# CPU.net
KiCad netlist of a schematic drawn in Altium Designer
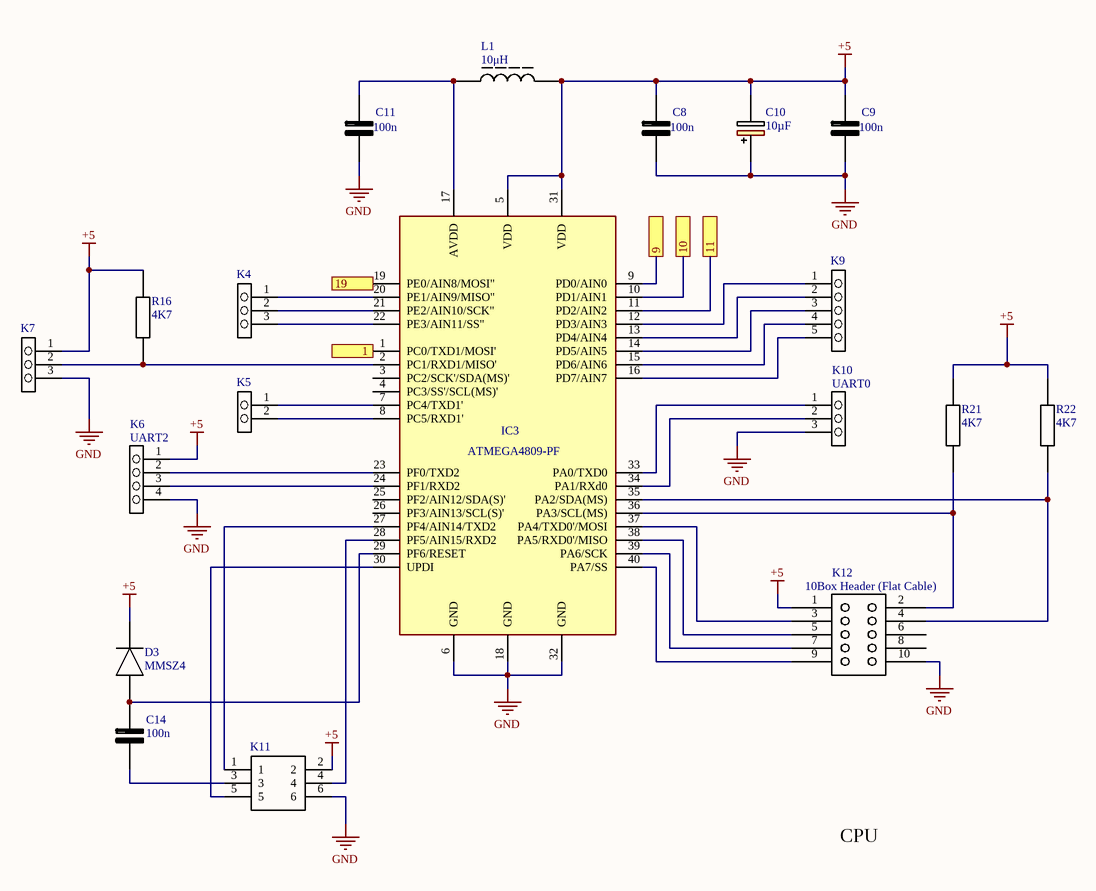
[diagram p0: CPU.SchDoc]

(export (version "E")
  (design (tool "Eeschema 10.0.6"))
  (components
    (comp (ref "C8")
      (value "100n")
      (footprint "SamacSys:C0805")
      (description "Capacitor")
      (fields (field (name "MANUFACTURER_PART_NUMBER") "C0805C391G3GACTU"))
      (libsource (lib "SamacSys") (part "0805_1"))
    )
    (comp (ref "C9")
      (value "100n")
      (footprint "SamacSys:C0805")
      (description "Capacitor")
      (fields (field (name "MANUFACTURER_PART_NUMBER") "C0805C391G3GACTU"))
      (libsource (lib "SamacSys") (part "0805_1"))
    )
    (comp (ref "C10")
      (value "10µF")
      (footprint "SamacSys:CAPPRD200W52D500H1250")
      (description "Capacitor Polarised")
      (fields
        (field (name "MOUSER2 PART NUMBER") "710-860020672010")
        (field (name "MANUFACTURER_PART_NUMBER") "860020672010")
      )
      (libsource (lib "SamacSys") (part "860020672010"))
    )
    (comp (ref "C11")
      (value "100n")
      (footprint "SamacSys:C0805")
      (description "Capacitor")
      (fields (field (name "MANUFACTURER_PART_NUMBER") "C0805C391G3GACTU"))
      (libsource (lib "SamacSys") (part "0805_1"))
    )
    (comp (ref "C14")
      (value "100n")
      (footprint "SamacSys:C0805")
      (description "Capacitor")
      (fields (field (name "MANUFACTURER_PART_NUMBER") "C0805C391G3GACTU"))
      (libsource (lib "SamacSys") (part "0805_1"))
    )
    (comp (ref "D3")
      (value "MMSZ4")
      (footprint "SamacSys:SOD2512X110N")
      (description "Diode")
      (fields
        (field (name "MOUSER2 PART NUMBER") "863-SMMDL914T1G")
        (field (name "MANUFACTURER_PART_NUMBER") "SMMDL914T1G")
      )
      (libsource (lib "SamacSys") (part "SMMDL914T1G"))
    )
    (comp (ref "IC3")
      (value "ATMEGA4809-PF")
      (footprint "SamacSys:DIP1543W58P254L5175H635Q40N")
      (description "Integrated Circuit")
      (fields (field (name "MOUSER2 PART NUMBER") "556-ATMEGA4809-PF"))
      (libsource (lib "SamacSys") (part "ATMEGA4809-PF"))
    )
    (comp (ref "K4")
      (value "M20-9990345")
      (footprint "SamacSys:HDRV3W64P0X254_1X3_762X254X864P")
      (description "Connector 3-PIN")
      (fields (field (name "MOUSER2 PART NUMBER") "855-M20-9990345"))
      (libsource (lib "SamacSys") (part "M20-9990345"))
    )
    (comp (ref "K5")
      (value "M20-9990246")
      (footprint "SamacSys:HDRV2W66P0X254_1X2_508X254X874P")
      (description "Connector 2-PIN")
      (fields (field (name "MOUSER2 PART NUMBER") "855-M20-9990246"))
      (libsource (lib "SamacSys") (part "M20-9990246"))
    )
    (comp (ref "K6")
      (value "UART2")
      (footprint "SamacSys:HDRV4W64P0X254_1X4_1016X254X834P")
      (description "Connector 4-PIN")
      (fields
        (field (name "MOUSER2 PART NUMBER") "855-M20-9770446")
        (field (name "MANUFACTURER_PART_NUMBER") "M20-9770446")
      )
      (libsource (lib "SamacSys") (part "M20-9770446"))
    )
    (comp (ref "K7")
      (value "M20-9990345")
      (footprint "SamacSys:HDRV3W64P0X254_1X3_762X254X864P")
      (description "Connector 3-PIN")
      (fields (field (name "MOUSER2 PART NUMBER") "855-M20-9990345"))
      (libsource (lib "SamacSys") (part "M20-9990345"))
    )
    (comp (ref "K9")
      (value "M20-9990545")
      (footprint "SamacSys:HDRV5W64P0X254_1X5_1270X254X864P")
      (description "Connector 5-PIN")
      (fields (field (name "MOUSER2 PART NUMBER") "855-M20-9990545"))
      (libsource (lib "SamacSys") (part "M20-9990545"))
    )
    (comp (ref "K10")
      (value "UART0")
      (footprint "SamacSys:HDRV3W64P0X254_1X3_762X254X864P")
      (description "Connector 3-PIN")
      (fields
        (field (name "MOUSER2 PART NUMBER") "855-M20-9990345")
        (field (name "MANUFACTURER_PART_NUMBER") "M20-9990345")
      )
      (libsource (lib "") (part "M20-9990345_1"))
    )
    (comp (ref "K11")
      (value "M20-9760342")
      (footprint "SamacSys:HDRV6W66P254_2X3_762X508X830P")
      (description "Connector 6-PIN")
      (libsource (lib "SamacSys") (part "M20-9760342"))
    )
    (comp (ref "K12")
      (value "10Box Header (Flat Cable)")
      (footprint "SamacSys:10BoxHeader")
      (libsource (lib "SamacSys") (part "10Box Header (Flat Cable)"))
    )
    (comp (ref "L1")
      (value "10μH")
      (footprint "SamacSys:VLS56045")
      (description "Inductor")
      (fields
        (field (name "MOUSER2 PART NUMBER") "810-VLS6045EX-100M-H")
        (field (name "MANUFACTURER_PART_NUMBER") "VLS6045EX-100M-H")
      )
      (libsource (lib "SamacSys") (part "VLS6045EX-100M-H"))
    )
    (comp (ref "R16")
      (value "4K7")
      (footprint "SamacSys:C0805")
      (description "Resistor")
      (fields (field (name "MANUFACTURER_PART_NUMBER") "C0805C391G3GACTU"))
      (libsource (lib "SamacSys") (part "0805"))
    )
    (comp (ref "R21")
      (value "4K7")
      (footprint "SamacSys:C0805")
      (description "Resistor")
      (fields (field (name "MANUFACTURER_PART_NUMBER") "C0805C391G3GACTU"))
      (libsource (lib "SamacSys") (part "0805"))
    )
    (comp (ref "R22")
      (value "4K7")
      (footprint "SamacSys:C0805")
      (description "Resistor")
      (fields (field (name "MANUFACTURER_PART_NUMBER") "C0805C391G3GACTU"))
      (libsource (lib "SamacSys") (part "0805"))
    )
  )
  (nets
    (net (code "1") (name "+5") (class "Default")
      (node (ref "C10") (pin "2") (pinfunction "-_2") (pintype "passive"))
      (node (ref "C8") (pin "2") (pinfunction "-_2") (pintype "passive"))
      (node (ref "C9") (pin "2") (pinfunction "-_2") (pintype "passive"))
      (node (ref "D3") (pin "1") (pinfunction "K_1") (pintype "passive"))
      (node (ref "IC3") (pin "31") (pinfunction "VDD_31") (pintype "passive"))
      (node (ref "IC3") (pin "5") (pinfunction "VDD_5") (pintype "passive"))
      (node (ref "K11") (pin "2") (pinfunction "2_2") (pintype "passive"))
      (node (ref "K12") (pin "1") (pinfunction "1_1") (pintype "passive"))
      (node (ref "K6") (pin "1") (pinfunction "1_1") (pintype "passive"))
      (node (ref "K7") (pin "1") (pinfunction "1_1") (pintype "passive"))
      (node (ref "L1") (pin "2") (pinfunction "2_2") (pintype "passive"))
      (node (ref "R16") (pin "2") (pinfunction "2_2") (pintype "passive"))
      (node (ref "R21") (pin "2") (pinfunction "2_2") (pintype "passive"))
      (node (ref "R22") (pin "2") (pinfunction "2_2") (pintype "passive"))
    )
    (net (code "2") (name "/1") (class "Default")
      (node (ref "IC3") (pin "1") (pinfunction "PC0/TXD1/MOSI'_1") (pintype "passive"))
    )
    (net (code "3") (name "/9") (class "Default")
      (node (ref "IC3") (pin "9") (pinfunction "PD0/AIN0_9") (pintype "passive"))
    )
    (net (code "4") (name "/10") (class "Default")
      (node (ref "IC3") (pin "10") (pinfunction "PD1/AIN1_10") (pintype "passive"))
    )
    (net (code "5") (name "/11") (class "Default")
      (node (ref "IC3") (pin "11") (pinfunction "PD2/AIN2_11") (pintype "passive"))
    )
    (net (code "6") (name "/19") (class "Default")
      (node (ref "IC3") (pin "19") (pinfunction "PE0/AIN8/MOSI\"_19") (pintype "passive"))
    )
    (net (code "7") (name "GND") (class "Default")
      (node (ref "C10") (pin "1") (pinfunction "+_1") (pintype "passive"))
      (node (ref "C11") (pin "1") (pinfunction "+_1") (pintype "passive"))
      (node (ref "C8") (pin "1") (pinfunction "+_1") (pintype "passive"))
      (node (ref "C9") (pin "1") (pinfunction "+_1") (pintype "passive"))
      (node (ref "IC3") (pin "18") (pinfunction "GND_18") (pintype "passive"))
      (node (ref "IC3") (pin "32") (pinfunction "GND_32") (pintype "passive"))
      (node (ref "IC3") (pin "6") (pinfunction "GND_6") (pintype "passive"))
      (node (ref "K10") (pin "3") (pinfunction "3_3") (pintype "passive"))
      (node (ref "K11") (pin "6") (pinfunction "6_6") (pintype "passive"))
      (node (ref "K12") (pin "10") (pinfunction "10_10") (pintype "passive"))
      (node (ref "K6") (pin "4") (pinfunction "4_4") (pintype "passive"))
      (node (ref "K7") (pin "3") (pinfunction "3_3") (pintype "passive"))
    )
    (net (code "8") (name "Net-(C11--)") (class "Default")
      (node (ref "C11") (pin "2") (pinfunction "-_2") (pintype "passive"))
      (node (ref "IC3") (pin "17") (pinfunction "AVDD_17") (pintype "passive"))
      (node (ref "L1") (pin "1") (pinfunction "1_1") (pintype "passive"))
    )
    (net (code "9") (name "Net-(C14-+)") (class "Default")
      (node (ref "C14") (pin "1") (pinfunction "+_1") (pintype "passive"))
      (node (ref "K11") (pin "3") (pinfunction "3_3") (pintype "passive"))
    )
    (net (code "10") (name "Net-(C14--)") (class "Default")
      (node (ref "C14") (pin "2") (pinfunction "-_2") (pintype "passive"))
      (node (ref "D3") (pin "2") (pinfunction "A_2") (pintype "passive"))
      (node (ref "IC3") (pin "29") (pinfunction "PF6/RESET_29") (pintype "passive"))
    )
    (net (code "11") (name "Net-(IC3-PA0{slash}TXD0)") (class "Default")
      (node (ref "IC3") (pin "33") (pinfunction "PA0/TXD0_33") (pintype "passive"))
      (node (ref "K10") (pin "1") (pinfunction "1_1") (pintype "passive"))
    )
    (net (code "12") (name "Net-(IC3-PA1{slash}RXd0)") (class "Default")
      (node (ref "IC3") (pin "34") (pinfunction "PA1/RXd0_34") (pintype "passive"))
      (node (ref "K10") (pin "2") (pinfunction "2_2") (pintype "passive"))
    )
    (net (code "13") (name "Net-(IC3-PA2{slash}SDA(MS))") (class "Default")
      (node (ref "IC3") (pin "35") (pinfunction "PA2/SDA(MS)_35") (pintype "passive"))
      (node (ref "K12") (pin "4") (pinfunction "4_4") (pintype "passive"))
      (node (ref "R22") (pin "1") (pinfunction "1_1") (pintype "passive"))
    )
    (net (code "14") (name "Net-(IC3-PA3{slash}SCL(MS))") (class "Default")
      (node (ref "IC3") (pin "36") (pinfunction "PA3/SCL(MS)_36") (pintype "passive"))
      (node (ref "K12") (pin "2") (pinfunction "2_2") (pintype "passive"))
      (node (ref "R21") (pin "1") (pinfunction "1_1") (pintype "passive"))
    )
    (net (code "15") (name "Net-(IC3-PA4{slash}TXD0'{slash}MOSI)") (class "Default")
      (node (ref "IC3") (pin "37") (pinfunction "PA4/TXD0'/MOSI_37") (pintype "passive"))
      (node (ref "K12") (pin "3") (pinfunction "3_3") (pintype "passive"))
    )
    (net (code "16") (name "Net-(IC3-PA5{slash}RXD0'{slash}MISO)") (class "Default")
      (node (ref "IC3") (pin "38") (pinfunction "PA5/RXD0'/MISO_38") (pintype "passive"))
      (node (ref "K12") (pin "5") (pinfunction "5_5") (pintype "passive"))
    )
    (net (code "17") (name "Net-(IC3-PA6{slash}SCK)") (class "Default")
      (node (ref "IC3") (pin "39") (pinfunction "PA6/SCK_39") (pintype "passive"))
      (node (ref "K12") (pin "7") (pinfunction "7_7") (pintype "passive"))
    )
    (net (code "18") (name "Net-(IC3-PA7{slash}SS)") (class "Default")
      (node (ref "IC3") (pin "40") (pinfunction "PA7/SS_40") (pintype "passive"))
      (node (ref "K12") (pin "9") (pinfunction "9_9") (pintype "passive"))
    )
    (net (code "19") (name "Net-(IC3-PC1{slash}RXD1{slash}MISO')") (class "Default")
      (node (ref "IC3") (pin "2") (pinfunction "PC1/RXD1/MISO'_2") (pintype "passive"))
      (node (ref "K7") (pin "2") (pinfunction "2_2") (pintype "passive"))
      (node (ref "R16") (pin "1") (pinfunction "1_1") (pintype "passive"))
    )
    (net (code "20") (name "Net-(IC3-PC4{slash}TXD1')") (class "Default")
      (node (ref "IC3") (pin "7") (pinfunction "PC4/TXD1'_7") (pintype "passive"))
      (node (ref "K5") (pin "1") (pinfunction "1_1") (pintype "passive"))
    )
    (net (code "21") (name "Net-(IC3-PC5{slash}RXD1')") (class "Default")
      (node (ref "IC3") (pin "8") (pinfunction "PC5/RXD1'_8") (pintype "passive"))
      (node (ref "K5") (pin "2") (pinfunction "2_2") (pintype "passive"))
    )
    (net (code "22") (name "Net-(IC3-PD3{slash}AIN3)") (class "Default")
      (node (ref "IC3") (pin "12") (pinfunction "PD3/AIN3_12") (pintype "passive"))
      (node (ref "K9") (pin "1") (pinfunction "1_1") (pintype "passive"))
    )
    (net (code "23") (name "Net-(IC3-PD4{slash}AIN4)") (class "Default")
      (node (ref "IC3") (pin "13") (pinfunction "PD4/AIN4_13") (pintype "passive"))
      (node (ref "K9") (pin "2") (pinfunction "2_2") (pintype "passive"))
    )
    (net (code "24") (name "Net-(IC3-PD5{slash}AIN5)") (class "Default")
      (node (ref "IC3") (pin "14") (pinfunction "PD5/AIN5_14") (pintype "passive"))
      (node (ref "K9") (pin "3") (pinfunction "3_3") (pintype "passive"))
    )
    (net (code "25") (name "Net-(IC3-PD6{slash}AIN6)") (class "Default")
      (node (ref "IC3") (pin "15") (pinfunction "PD6/AIN6_15") (pintype "passive"))
      (node (ref "K9") (pin "4") (pinfunction "4_4") (pintype "passive"))
    )
    (net (code "26") (name "Net-(IC3-PD7{slash}AIN7)") (class "Default")
      (node (ref "IC3") (pin "16") (pinfunction "PD7/AIN7_16") (pintype "passive"))
      (node (ref "K9") (pin "5") (pinfunction "5_5") (pintype "passive"))
    )
    (net (code "27") (name "Net-(IC3-PE1{slash}AIN9{slash}MISO\")") (class "Default")
      (node (ref "IC3") (pin "20") (pinfunction "PE1/AIN9/MISO\"_20") (pintype "passive"))
      (node (ref "K4") (pin "1") (pinfunction "1_1") (pintype "passive"))
    )
    (net (code "28") (name "Net-(IC3-PE2{slash}AIN10{slash}SCK\")") (class "Default")
      (node (ref "IC3") (pin "21") (pinfunction "PE2/AIN10/SCK\"_21") (pintype "passive"))
      (node (ref "K4") (pin "2") (pinfunction "2_2") (pintype "passive"))
    )
    (net (code "29") (name "Net-(IC3-PE3{slash}AIN11{slash}SS\")") (class "Default")
      (node (ref "IC3") (pin "22") (pinfunction "PE3/AIN11/SS\"_22") (pintype "passive"))
      (node (ref "K4") (pin "3") (pinfunction "3_3") (pintype "passive"))
    )
    (net (code "30") (name "Net-(IC3-PF0{slash}TXD2)") (class "Default")
      (node (ref "IC3") (pin "23") (pinfunction "PF0/TXD2_23") (pintype "passive"))
      (node (ref "K6") (pin "2") (pinfunction "2_2") (pintype "passive"))
    )
    (net (code "31") (name "Net-(IC3-PF1{slash}RXD2)") (class "Default")
      (node (ref "IC3") (pin "24") (pinfunction "PF1/RXD2_24") (pintype "passive"))
      (node (ref "K6") (pin "3") (pinfunction "3_3") (pintype "passive"))
    )
    (net (code "32") (name "Net-(IC3-PF4{slash}AIN14{slash}TXD2)") (class "Default")
      (node (ref "IC3") (pin "27") (pinfunction "PF4/AIN14/TXD2_27") (pintype "passive"))
      (node (ref "K11") (pin "1") (pinfunction "1_1") (pintype "passive"))
    )
    (net (code "33") (name "Net-(IC3-PF5{slash}AIN15{slash}RXD2)") (class "Default")
      (node (ref "IC3") (pin "28") (pinfunction "PF5/AIN15/RXD2_28") (pintype "passive"))
      (node (ref "K11") (pin "4") (pinfunction "4_4") (pintype "passive"))
    )
    (net (code "34") (name "Net-(IC3-UPDI)") (class "Default")
      (node (ref "IC3") (pin "30") (pinfunction "UPDI_30") (pintype "passive"))
      (node (ref "K11") (pin "5") (pinfunction "5_5") (pintype "passive"))
    )
    (net (code "35") (name "unconnected-(IC3-PC2{slash}SCK'{slash}SDA(MS)'-Pad3)") (class "Default")
      (node (ref "IC3") (pin "3") (pinfunction "PC2/SCK'/SDA(MS)'_3") (pintype "passive"))
    )
    (net (code "36") (name "unconnected-(IC3-PC3{slash}SS'{slash}SCL(MS)'-Pad4)") (class "Default")
      (node (ref "IC3") (pin "4") (pinfunction "PC3/SS'/SCL(MS)'_4") (pintype "passive"))
    )
    (net (code "37") (name "unconnected-(IC3-PF2{slash}AIN12{slash}SDA(S)'-Pad25)") (class "Default")
      (node (ref "IC3") (pin "25") (pinfunction "PF2/AIN12/SDA(S)'_25") (pintype "passive"))
    )
    (net (code "38") (name "unconnected-(IC3-PF3{slash}AIN13{slash}SCL(S)'-Pad26)") (class "Default")
      (node (ref "IC3") (pin "26") (pinfunction "PF3/AIN13/SCL(S)'_26") (pintype "passive"))
    )
    (net (code "39") (name "unconnected-(K12-Pad6)") (class "Default")
      (node (ref "K12") (pin "6") (pinfunction "6_6") (pintype "passive"))
    )
    (net (code "40") (name "unconnected-(K12-Pad8)") (class "Default")
      (node (ref "K12") (pin "8") (pinfunction "8_8") (pintype "passive"))
    )
  )
)
